# DM1098LUXD-LITE_USB.net
KiCad netlist of a schematic drawn in Altium Designer
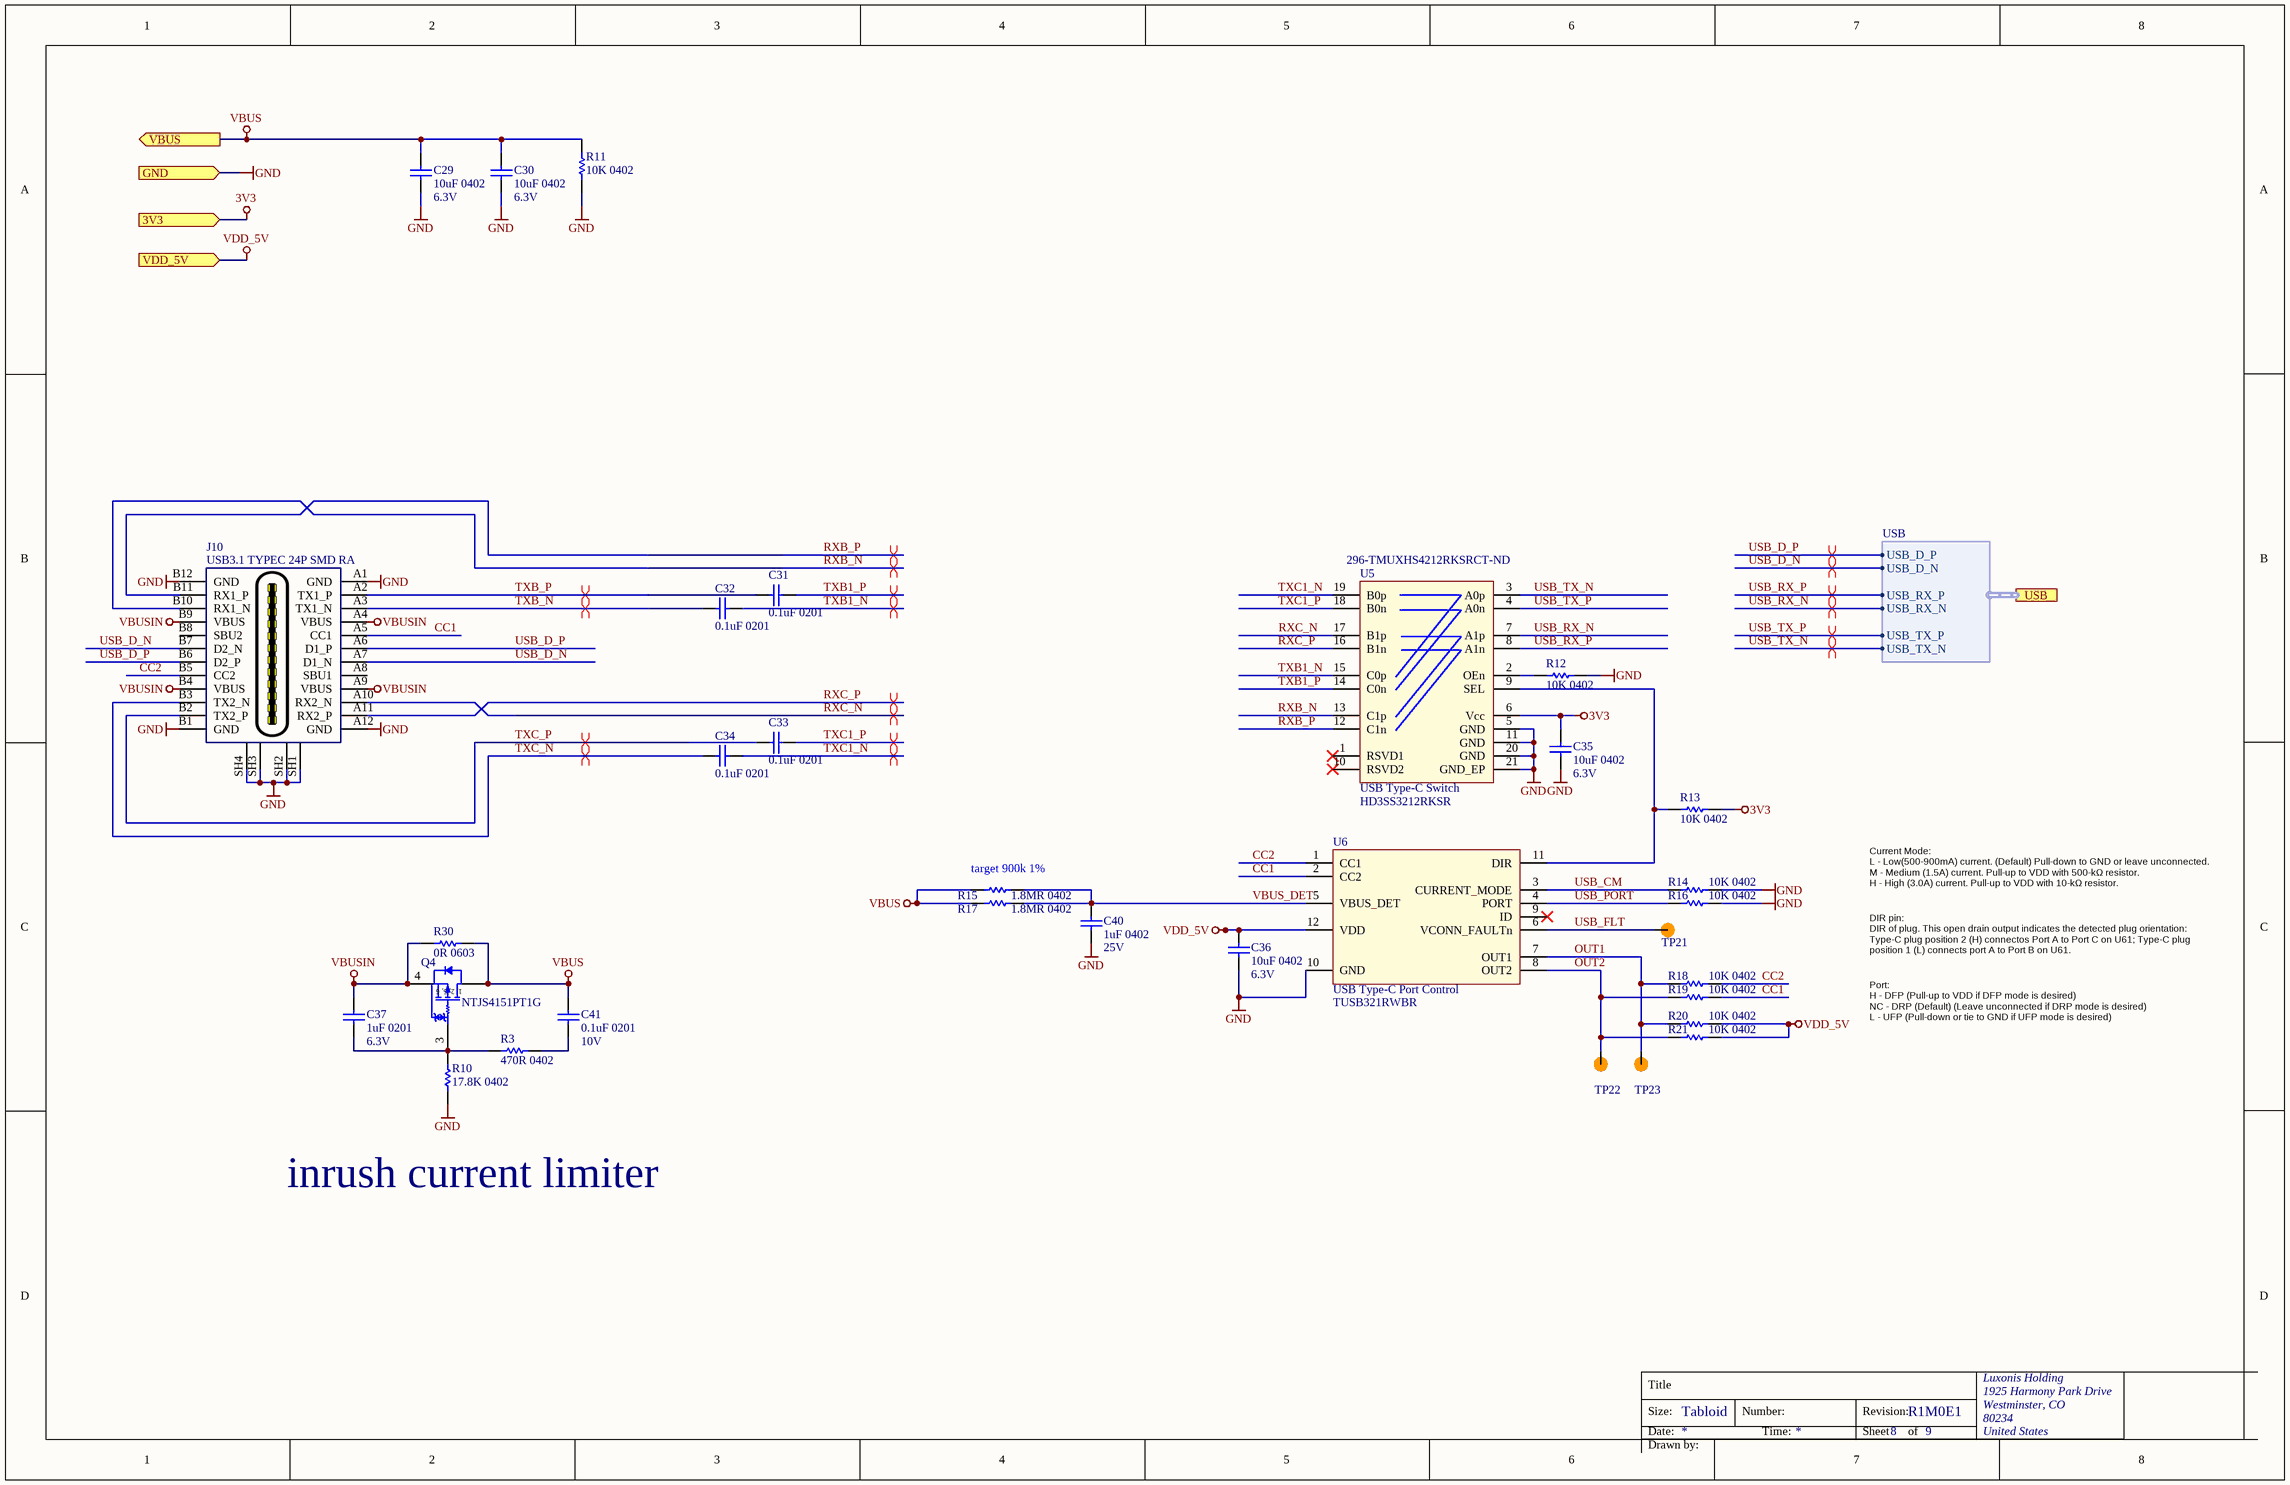
[diagram p0: DM1098LUXD-LITE_USB.SchDoc]

(export (version "E")
  (design (tool "Eeschema 10.0.6"))
  (components
    (comp (ref "C29")
      (value "10uF 0402")
      (footprint "CAP_Altium_Vault_Generic:CAPC0402(1005)70_L")
      (description "CAP CER 10UF 6.3V X5R 0402 20%")
      (fields (field (name "TOLERANCE") "20%") (field (name "VOLTAGE RATING") "6.3V"))
      (libsource (lib "LuxonisMaster") (part "GRM155R60J106ME15D"))
    )
    (comp (ref "C30")
      (value "10uF 0402")
      (footprint "CAP_Altium_Vault_Generic:CAPC0402(1005)70_L")
      (description "CAP CER 10UF 6.3V X5R 0402 20%")
      (fields (field (name "TOLERANCE") "20%") (field (name "VOLTAGE RATING") "6.3V"))
      (libsource (lib "LuxonisMaster") (part "GRM155R60J106ME15D"))
    )
    (comp (ref "C31")
      (value "0.1uF 0201")
      (footprint "CAP_Altium_Vault_Generic:CAPC0201(0603)33_L")
      (description "CAP CER 0.1UF 10V X5R 0201")
      (fields (field (name "TOLERANCE") "10%") (field (name "VOLTAGE") "10V"))
      (libsource (lib "LuxonisMaster") (part "GRM033R61A104KE15D"))
    )
    (comp (ref "C32")
      (value "0.1uF 0201")
      (footprint "CAP_Altium_Vault_Generic:CAPC0201(0603)33_L")
      (description "CAP CER 0.1UF 10V X5R 0201")
      (fields (field (name "TOLERANCE") "10%") (field (name "VOLTAGE") "10V"))
      (libsource (lib "LuxonisMaster") (part "GRM033R61A104KE15D"))
    )
    (comp (ref "C33")
      (value "0.1uF 0201")
      (footprint "CAP_Altium_Vault_Generic:CAPC0201(0603)33_L")
      (description "CAP CER 0.1UF 10V X5R 0201")
      (fields (field (name "TOLERANCE") "10%") (field (name "VOLTAGE") "10V"))
      (libsource (lib "LuxonisMaster") (part "GRM033R61A104KE15D"))
    )
    (comp (ref "C34")
      (value "0.1uF 0201")
      (footprint "CAP_Altium_Vault_Generic:CAPC0201(0603)33_L")
      (description "CAP CER 0.1UF 10V X5R 0201")
      (fields (field (name "TOLERANCE") "10%") (field (name "VOLTAGE") "10V"))
      (libsource (lib "LuxonisMaster") (part "GRM033R61A104KE15D"))
    )
    (comp (ref "C35")
      (value "10uF 0402")
      (footprint "CAP_Altium_Vault_Generic:CAPC0402(1005)70_L")
      (description "CAP CER 10UF 6.3V X5R 0402 20%")
      (fields (field (name "TOLERANCE") "20%") (field (name "VOLTAGE RATING") "6.3V"))
      (libsource (lib "LuxonisMaster") (part "GRM155R60J106ME15D"))
    )
    (comp (ref "C36")
      (value "10uF 0402")
      (footprint "CAP_Altium_Vault_Generic:CAPC0402(1005)70_L")
      (description "CAP CER 10UF 6.3V X5R 0402 20%")
      (fields (field (name "TOLERANCE") "20%") (field (name "VOLTAGE RATING") "6.3V"))
      (libsource (lib "LuxonisMaster") (part "GRM155R60J106ME15D"))
    )
    (comp (ref "C37")
      (value "1uF 0201")
      (footprint "CAP_Altium_Vault_Generic:CAPC0201(0603)33_N")
      (description "CAP CER 1UF 6.3V X5R 0201 20%")
      (fields (field (name "TOLERANCE") "20%") (field (name "VOLTAGE") "6.3V"))
      (libsource (lib "LuxonisMaster") (part "GRM033R60J105MEA2D"))
    )
    (comp (ref "C40")
      (value "1uF 0402")
      (footprint "CAP_Altium_Vault_Generic:CAPC0402(1005)70_N")
      (description "CAP CER 1UF 25V X5R 0402 10%")
      (fields
        (field (name "TOLERANCE") "10%")
        (field (name "VOLTAGE") "25V")
        (field (name "VOLTAGE RATING") "25V")
      )
      (libsource (lib "LuxonisMaster") (part "GRM155R61E105KA12D"))
    )
    (comp (ref "C41")
      (value "0.1uF 0201")
      (footprint "CAP_Altium_Vault_Generic:CAPC0201(0603)33_N")
      (description "CAP CER 0.1UF 10V X5R 0201")
      (fields (field (name "TOLERANCE") "10%") (field (name "VOLTAGE") "10V"))
      (libsource (lib "LuxonisMaster") (part "GRM033R61A104KE15D"))
    )
    (comp (ref "J10")
      (value "USB3.1 TYPEC 24P SMD RA")
      (footprint "LuxonisMaster:105450-0101")
      (description "CONN RCP USB3.1 TYPEC 24P SMD RA")
      (libsource (lib "LuxonisMaster") (part "105450-0101"))
    )
    (comp (ref "Q4")
      (value "NTJS4151PT1G")
      (footprint "ONSC-SC70-6-419B-02_W_V")
      (description "Trench Power MOSFET, -20 V, -4.2 A, Single P-Channel, 6-Pin SC70, Pb-Free, Tape and Reel")
      (libsource (lib "DM1098LUXD-LITE") (part "NTJS4151PT1G"))
    )
    (comp (ref "R3")
      (value "470R 0402")
      (footprint "RES_Altium_Vault_Generic:RESC0402(1005)_L")
      (description "RES SMD 470 OHM 1% 1/16W 0402")
      (fields (field (name "TOLERANCE") "1%"))
      (libsource (lib "LuxonisMaster") (part "CRCW0402470RFKED"))
    )
    (comp (ref "R10")
      (value "17.8K 0402")
      (footprint "RES_Altium_Vault_Generic:RESC0402(1005)_L")
      (fields (field (name "TOLERANCE") "1%"))
      (libsource (lib "LuxonisMaster") (part "ERJ-2RKF1782X"))
    )
    (comp (ref "R11")
      (value "10K 0402")
      (footprint "RES_Altium_Vault_Generic:RESC0402(1005)_L")
      (fields (field (name "TOLERANCE") "1%"))
      (libsource (lib "LuxonisMaster") (part "RC0402FR-1310KL"))
    )
    (comp (ref "R12")
      (value "10K 0402")
      (footprint "RES_Altium_Vault_Generic:RESC0402(1005)_L")
      (fields (field (name "TOLERANCE") "1%"))
      (libsource (lib "LuxonisMaster") (part "RC0402FR-1310KL"))
    )
    (comp (ref "R13")
      (value "10K 0402")
      (footprint "RES_Altium_Vault_Generic:RESC0402(1005)_L")
      (fields (field (name "TOLERANCE") "1%"))
      (libsource (lib "LuxonisMaster") (part "RC0402FR-1310KL"))
    )
    (comp (ref "R14")
      (value "10K 0402")
      (footprint "RES_Altium_Vault_Generic:RESC0402(1005)_L")
      (fields (field (name "TOLERANCE") "1%"))
      (libsource (lib "LuxonisMaster") (part "RC0402FR-1310KL"))
    )
    (comp (ref "R15")
      (value "1.8MR 0402")
      (footprint "RES_Altium_Vault_Generic:RESC0402(1005)_L")
      (description "RES SMD 1.8M OHM 1% 1/16W 0402")
      (fields (field (name "TOLERANCE") "1%"))
      (libsource (lib "LuxonisMaster") (part "CRCW04021M80FKED"))
    )
    (comp (ref "R16")
      (value "10K 0402")
      (footprint "RES_Altium_Vault_Generic:RESC0402(1005)_L")
      (fields (field (name "TOLERANCE") "1%"))
      (libsource (lib "LuxonisMaster") (part "RC0402FR-1310KL"))
    )
    (comp (ref "R17")
      (value "1.8MR 0402")
      (footprint "RES_Altium_Vault_Generic:RESC0402(1005)_L")
      (description "RES SMD 1.8M OHM 1% 1/16W 0402")
      (fields (field (name "TOLERANCE") "1%"))
      (libsource (lib "LuxonisMaster") (part "CRCW04021M80FKED"))
    )
    (comp (ref "R18")
      (value "10K 0402")
      (footprint "RES_Altium_Vault_Generic:RESC0402(1005)_L")
      (fields (field (name "TOLERANCE") "1%"))
      (libsource (lib "LuxonisMaster") (part "RC0402FR-1310KL"))
    )
    (comp (ref "R19")
      (value "10K 0402")
      (footprint "RES_Altium_Vault_Generic:RESC0402(1005)_L")
      (fields (field (name "TOLERANCE") "1%"))
      (libsource (lib "LuxonisMaster") (part "RC0402FR-1310KL"))
    )
    (comp (ref "R20")
      (value "10K 0402")
      (footprint "RES_Altium_Vault_Generic:RESC0402(1005)_L")
      (fields (field (name "TOLERANCE") "1%"))
      (libsource (lib "LuxonisMaster") (part "RC0402FR-1310KL"))
    )
    (comp (ref "R21")
      (value "10K 0402")
      (footprint "RES_Altium_Vault_Generic:RESC0402(1005)_L")
      (fields (field (name "TOLERANCE") "1%"))
      (libsource (lib "LuxonisMaster") (part "RC0402FR-1310KL"))
    )
    (comp (ref "R30")
      (value "0R 0603")
      (footprint "RES_Altium_Vault_Generic:RESC0603(1608)_N")
      (fields (field (name "TOLERANCE") "5%"))
      (libsource (lib "LuxonisMaster") (part "CRCW06030000Z0EA"))
    )
    (comp (ref "TP21")
      (value "TP100_200_NS")
      (footprint "LuxonisMaster:TP100_200_NS")
      (libsource (lib "LuxonisMaster") (part "TEST_POINT"))
    )
    (comp (ref "TP22")
      (value "TP100_200_NS")
      (footprint "LuxonisMaster:TP100_200_NS")
      (libsource (lib "LuxonisMaster") (part "TEST_POINT"))
    )
    (comp (ref "TP23")
      (value "TP100_200_NS")
      (footprint "LuxonisMaster:TP100_200_NS")
      (libsource (lib "LuxonisMaster") (part "TEST_POINT"))
    )
    (comp (ref "U5")
      (value "USB Type-C Switch")
      (footprint "LuxonisMaster:HD3SS3212RKSR")
      (description "Differential Multiplexer, 1 Func, 2 Channel, PQCC20")
      (fields
        (field (name "MANUFACTURER PART NUMBER 1") "HD3SS3212RKSR")
        (field (name "SUPPLIER PART NUMBER 2") "296-TMUXHS4212RKSRCT-ND")
      )
      (libsource (lib "LuxonisMaster") (part "HD3SS3212RKSR"))
    )
    (comp (ref "U6")
      (value "USB Type-C Port Control")
      (footprint "LuxonisMaster:TUSB321RWBR")
      (description "IC USB PORT CONTROL TYPE-C 12X2Q")
      (fields (field (name "MANUFACTURER PART NUMBER 1") "TUSB321RWBR"))
      (libsource (lib "LuxonisMaster") (part "TUSB321RWBR"))
    )
  )
  (nets
    (net (code "2") (name "/CC1") (class "Default")
      (node (ref "J10") (pin "A5") (pinfunction "CC1_A5") (pintype "passive"))
      (node (ref "R19") (pin "2") (pinfunction "2_2") (pintype "passive"))
      (node (ref "U6") (pin "2") (pinfunction "CC2_2") (pintype "passive"))
    )
    (net (code "3") (name "/CC2") (class "Default")
      (node (ref "J10") (pin "B5") (pinfunction "CC2_B5") (pintype "passive"))
      (node (ref "R18") (pin "2") (pinfunction "2_2") (pintype "passive"))
      (node (ref "U6") (pin "1") (pinfunction "CC1_1") (pintype "passive"))
    )
    (net (code "4") (name "/OUT1") (class "Default")
      (node (ref "R18") (pin "1") (pinfunction "1_1") (pintype "passive"))
      (node (ref "R20") (pin "1") (pinfunction "1_1") (pintype "passive"))
      (node (ref "TP23") (pin "1") (pintype "passive"))
      (node (ref "U6") (pin "7") (pinfunction "OUT1_7") (pintype "passive"))
    )
    (net (code "5") (name "/OUT2") (class "Default")
      (node (ref "R19") (pin "1") (pinfunction "1_1") (pintype "passive"))
      (node (ref "R21") (pin "1") (pinfunction "1_1") (pintype "passive"))
      (node (ref "TP22") (pin "1") (pintype "passive"))
      (node (ref "U6") (pin "8") (pinfunction "OUT2_8") (pintype "passive"))
    )
    (net (code "6") (name "/RXB_N") (class "Default")
      (node (ref "J10") (pin "B10") (pinfunction "RX1_N_B10") (pintype "passive"))
      (node (ref "U5") (pin "13") (pinfunction "C1p_13") (pintype "passive"))
    )
    (net (code "7") (name "/RXB_P") (class "Default")
      (node (ref "J10") (pin "B11") (pinfunction "RX1_P_B11") (pintype "passive"))
      (node (ref "U5") (pin "12") (pinfunction "C1n_12") (pintype "passive"))
    )
    (net (code "8") (name "/RXC_N") (class "Default")
      (node (ref "J10") (pin "A10") (pinfunction "RX2_N_A10") (pintype "passive"))
      (node (ref "U5") (pin "17") (pinfunction "B1p_17") (pintype "passive"))
    )
    (net (code "9") (name "/RXC_P") (class "Default")
      (node (ref "J10") (pin "A11") (pinfunction "RX2_P_A11") (pintype "passive"))
      (node (ref "U5") (pin "16") (pinfunction "B1n_16") (pintype "passive"))
    )
    (net (code "10") (name "/TXB1_N") (class "Default")
      (node (ref "C32") (pin "2") (pinfunction "2_2") (pintype "passive"))
      (node (ref "U5") (pin "15") (pinfunction "C0p_15") (pintype "passive"))
    )
    (net (code "11") (name "/TXB1_P") (class "Default")
      (node (ref "C31") (pin "2") (pinfunction "2_2") (pintype "passive"))
      (node (ref "U5") (pin "14") (pinfunction "C0n_14") (pintype "passive"))
    )
    (net (code "12") (name "/TXB_N") (class "Default")
      (node (ref "C32") (pin "1") (pinfunction "1_1") (pintype "passive"))
      (node (ref "J10") (pin "A3") (pinfunction "TX1_N_A3") (pintype "passive"))
    )
    (net (code "13") (name "/TXB_P") (class "Default")
      (node (ref "C31") (pin "1") (pinfunction "1_1") (pintype "passive"))
      (node (ref "J10") (pin "A2") (pinfunction "TX1_P_A2") (pintype "passive"))
    )
    (net (code "14") (name "/TXC1_N") (class "Default")
      (node (ref "C34") (pin "2") (pinfunction "2_2") (pintype "passive"))
      (node (ref "U5") (pin "19") (pinfunction "B0p_19") (pintype "passive"))
    )
    (net (code "15") (name "/TXC1_P") (class "Default")
      (node (ref "C33") (pin "2") (pinfunction "2_2") (pintype "passive"))
      (node (ref "U5") (pin "18") (pinfunction "B0n_18") (pintype "passive"))
    )
    (net (code "16") (name "/TXC_N") (class "Default")
      (node (ref "C34") (pin "1") (pinfunction "1_1") (pintype "passive"))
      (node (ref "J10") (pin "B3") (pinfunction "TX2_N_B3") (pintype "passive"))
    )
    (net (code "17") (name "/TXC_P") (class "Default")
      (node (ref "C33") (pin "1") (pinfunction "1_1") (pintype "passive"))
      (node (ref "J10") (pin "B2") (pinfunction "TX2_P_B2") (pintype "passive"))
    )
    (net (code "18") (name "/USB_CM") (class "Default")
      (node (ref "R14") (pin "1") (pinfunction "1_1") (pintype "passive"))
      (node (ref "U6") (pin "3") (pinfunction "CURRENT_MODE_3") (pintype "passive"))
    )
    (net (code "19") (name "/USB_D_N") (class "Default")
      (node (ref "J10") (pin "A7") (pinfunction "D1_N_A7") (pintype "passive"))
      (node (ref "J10") (pin "B7") (pinfunction "D2_N_B7") (pintype "passive"))
    )
    (net (code "20") (name "/USB_D_P") (class "Default")
      (node (ref "J10") (pin "A6") (pinfunction "D1_P_A6") (pintype "passive"))
      (node (ref "J10") (pin "B6") (pinfunction "D2_P_B6") (pintype "passive"))
    )
    (net (code "21") (name "/USB_FLT") (class "Default")
      (node (ref "TP21") (pin "1") (pintype "passive"))
      (node (ref "U6") (pin "6") (pinfunction "VCONN_FAULTn_6") (pintype "passive"))
    )
    (net (code "22") (name "/USB_PORT") (class "Default")
      (node (ref "R16") (pin "1") (pinfunction "1_1") (pintype "passive"))
      (node (ref "U6") (pin "4") (pinfunction "PORT_4") (pintype "passive"))
    )
    (net (code "23") (name "/USB_RX_N") (class "Default")
      (node (ref "U5") (pin "7") (pinfunction "A1p_7") (pintype "passive"))
    )
    (net (code "24") (name "/USB_RX_P") (class "Default")
      (node (ref "U5") (pin "8") (pinfunction "A1n_8") (pintype "passive"))
    )
    (net (code "25") (name "/USB_TX_N") (class "Default")
      (node (ref "U5") (pin "3") (pinfunction "A0p_3") (pintype "passive"))
    )
    (net (code "26") (name "/USB_TX_P") (class "Default")
      (node (ref "U5") (pin "4") (pinfunction "A0n_4") (pintype "passive"))
    )
    (net (code "27") (name "/VBUS_DET") (class "Default")
      (node (ref "C40") (pin "2") (pinfunction "2_2") (pintype "passive"))
      (node (ref "R15") (pin "2") (pinfunction "2_2") (pintype "passive"))
      (node (ref "R17") (pin "2") (pinfunction "2_2") (pintype "passive"))
      (node (ref "U6") (pin "5") (pinfunction "VBUS_DET_5") (pintype "passive"))
    )
    (net (code "29") (name "3V3") (class "Default")
      (node (ref "C35") (pin "2") (pinfunction "2_2") (pintype "passive"))
      (node (ref "R13") (pin "2") (pinfunction "2_2") (pintype "passive"))
      (node (ref "U5") (pin "6") (pinfunction "Vcc_6") (pintype "passive"))
    )
    (net (code "30") (name "GND") (class "Default")
      (node (ref "C29") (pin "1") (pinfunction "1_1") (pintype "passive"))
      (node (ref "C30") (pin "1") (pinfunction "1_1") (pintype "passive"))
      (node (ref "C35") (pin "1") (pinfunction "1_1") (pintype "passive"))
      (node (ref "C36") (pin "1") (pinfunction "1_1") (pintype "passive"))
      (node (ref "C40") (pin "1") (pinfunction "1_1") (pintype "passive"))
      (node (ref "J10") (pin "A1") (pinfunction "GND_A1") (pintype "passive"))
      (node (ref "J10") (pin "A12") (pinfunction "GND_A12") (pintype "passive"))
      (node (ref "J10") (pin "B1") (pinfunction "GND_B1") (pintype "passive"))
      (node (ref "J10") (pin "B12") (pinfunction "GND_B12") (pintype "passive"))
      (node (ref "J10") (pin "SH1") (pinfunction "SH_SH1") (pintype "passive"))
      (node (ref "J10") (pin "SH2") (pinfunction "SH_SH2") (pintype "passive"))
      (node (ref "J10") (pin "SH3") (pinfunction "SH_SH3") (pintype "passive"))
      (node (ref "J10") (pin "SH4") (pinfunction "SH_SH4") (pintype "passive"))
      (node (ref "R10") (pin "1") (pinfunction "1_1") (pintype "passive"))
      (node (ref "R11") (pin "1") (pinfunction "1_1") (pintype "passive"))
      (node (ref "R12") (pin "2") (pinfunction "2_2") (pintype "passive"))
      (node (ref "R14") (pin "2") (pinfunction "2_2") (pintype "passive"))
      (node (ref "R16") (pin "2") (pinfunction "2_2") (pintype "passive"))
      (node (ref "U5") (pin "11") (pinfunction "GND_11") (pintype "passive"))
      (node (ref "U5") (pin "20") (pinfunction "GND_20") (pintype "passive"))
      (node (ref "U5") (pin "21") (pinfunction "GND_EP_21") (pintype "passive"))
      (node (ref "U5") (pin "5") (pinfunction "GND_5") (pintype "passive"))
      (node (ref "U6") (pin "10") (pinfunction "GND_10") (pintype "passive"))
    )
    (net (code "31") (name "Net-(C41-Pad1)") (class "Default")
      (node (ref "C41") (pin "1") (pinfunction "1_1") (pintype "passive"))
      (node (ref "R3") (pin "2") (pinfunction "2_2") (pintype "passive"))
    )
    (net (code "32") (name "Net-(Q4-G)") (class "Default")
      (node (ref "C37") (pin "1") (pinfunction "1_1") (pintype "passive"))
      (node (ref "Q4") (pin "3") (pinfunction "G_3") (pintype "passive"))
      (node (ref "R10") (pin "2") (pinfunction "2_2") (pintype "passive"))
      (node (ref "R3") (pin "1") (pinfunction "1_1") (pintype "passive"))
    )
    (net (code "33") (name "Net-(U5-OEn)") (class "Default")
      (node (ref "R12") (pin "1") (pinfunction "1_1") (pintype "passive"))
      (node (ref "U5") (pin "2") (pinfunction "OEn_2") (pintype "passive"))
    )
    (net (code "34") (name "Net-(U5-SEL)") (class "Default")
      (node (ref "R13") (pin "1") (pinfunction "1_1") (pintype "passive"))
      (node (ref "U5") (pin "9") (pinfunction "SEL_9") (pintype "passive"))
      (node (ref "U6") (pin "11") (pinfunction "DIR_11") (pintype "passive"))
    )
    (net (code "35") (name "VBUS") (class "Default")
      (node (ref "C29") (pin "2") (pinfunction "2_2") (pintype "passive"))
      (node (ref "C30") (pin "2") (pinfunction "2_2") (pintype "passive"))
      (node (ref "C41") (pin "2") (pinfunction "2_2") (pintype "passive"))
      (node (ref "Q4") (pin "1") (pinfunction "D_1") (pintype "passive"))
      (node (ref "Q4") (pin "2") (pinfunction "D_2") (pintype "passive"))
      (node (ref "Q4") (pin "5") (pinfunction "D_5") (pintype "passive"))
      (node (ref "Q4") (pin "6") (pinfunction "D_6") (pintype "passive"))
      (node (ref "R11") (pin "2") (pinfunction "2_2") (pintype "passive"))
      (node (ref "R15") (pin "1") (pinfunction "1_1") (pintype "passive"))
      (node (ref "R17") (pin "1") (pinfunction "1_1") (pintype "passive"))
      (node (ref "R30") (pin "2") (pinfunction "2_2") (pintype "passive"))
    )
    (net (code "36") (name "VBUSIN") (class "Default")
      (node (ref "C37") (pin "2") (pinfunction "2_2") (pintype "passive"))
      (node (ref "J10") (pin "A4") (pinfunction "VBUS_A4") (pintype "passive"))
      (node (ref "J10") (pin "A9") (pinfunction "VBUS_A9") (pintype "passive"))
      (node (ref "J10") (pin "B4") (pinfunction "VBUS_B4") (pintype "passive"))
      (node (ref "J10") (pin "B9") (pinfunction "VBUS_B9") (pintype "passive"))
      (node (ref "Q4") (pin "4") (pinfunction "S_4") (pintype "passive"))
      (node (ref "R30") (pin "1") (pinfunction "1_1") (pintype "passive"))
    )
    (net (code "37") (name "VDD_5V") (class "Default")
      (node (ref "C36") (pin "2") (pinfunction "2_2") (pintype "passive"))
      (node (ref "R20") (pin "2") (pinfunction "2_2") (pintype "passive"))
      (node (ref "R21") (pin "2") (pinfunction "2_2") (pintype "passive"))
      (node (ref "U6") (pin "12") (pinfunction "VDD_12") (pintype "passive"))
    )
    (net (code "38") (name "unconnected-(J10-SBU1-PadA8)") (class "Default")
      (node (ref "J10") (pin "A8") (pinfunction "SBU1_A8") (pintype "passive"))
    )
    (net (code "39") (name "unconnected-(J10-SBU2-PadB8)") (class "Default")
      (node (ref "J10") (pin "B8") (pinfunction "SBU2_B8") (pintype "passive"))
    )
    (net (code "40") (name "unconnected-(U5-RSVD1-Pad1)") (class "Default")
      (node (ref "U5") (pin "1") (pinfunction "RSVD1_1") (pintype "passive+no_connect"))
    )
    (net (code "41") (name "unconnected-(U5-RSVD2-Pad10)") (class "Default")
      (node (ref "U5") (pin "10") (pinfunction "RSVD2_10") (pintype "passive+no_connect"))
    )
    (net (code "42") (name "unconnected-(U6-ID-Pad9)") (class "Default")
      (node (ref "U6") (pin "9") (pinfunction "ID_9") (pintype "passive+no_connect"))
    )
  )
)
